# DAC_SUPPLY.net
KiCad netlist of a schematic drawn in Altium Designer
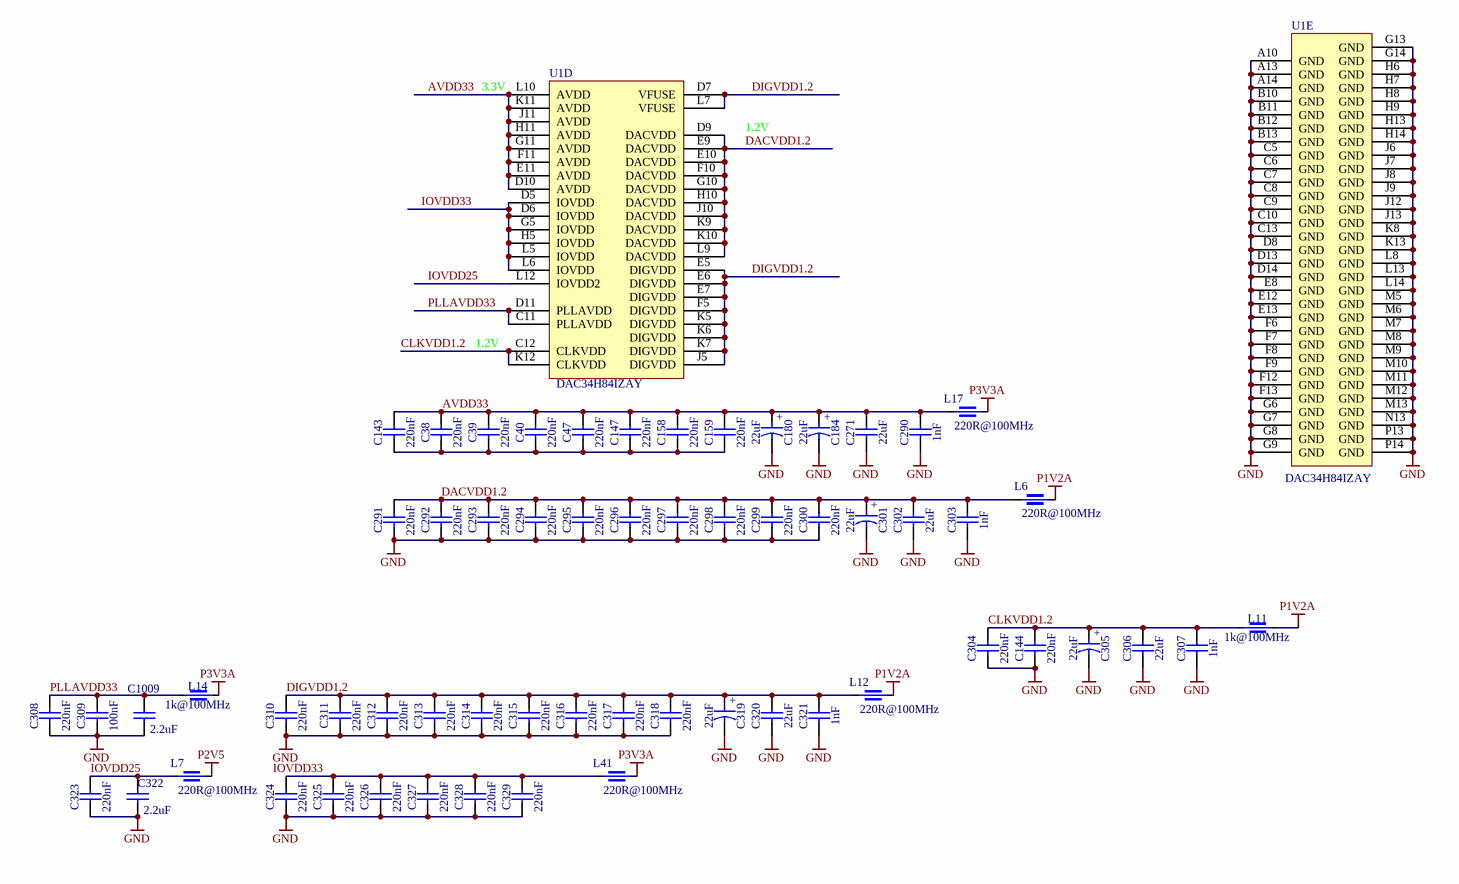
[diagram p0: DAC_SUPPLY.SchDoc]

(export (version "E")
  (design (tool "Eeschema 10.0.6"))
  (components
    (comp (ref "C38")
      (value "220nF")
      (footprint "CAPC0603X33N")
      (description "Non-polarised capacitor")
      (fields
        (field (name "PART NUMBER") "CC0201_220NF_6.3V_20%_X5R")
        (field (name "VOLTAGE") "6.3V")
        (field (name "AUTHOR") "CERN DEM JLC")
      )
      (libsource (lib "Capacitors") (part "Capacitor - non polarized"))
    )
    (comp (ref "C39")
      (value "220nF")
      (footprint "CAPC0603X33N")
      (description "Non-polarised capacitor")
      (fields
        (field (name "PART NUMBER") "CC0201_220NF_6.3V_20%_X5R")
        (field (name "VOLTAGE") "6.3V")
        (field (name "AUTHOR") "CERN DEM JLC")
      )
      (libsource (lib "Capacitors") (part "Capacitor - non polarized"))
    )
    (comp (ref "C40")
      (value "220nF")
      (footprint "CAPC0603X33N")
      (description "Non-polarised capacitor")
      (fields
        (field (name "PART NUMBER") "CC0201_220NF_6.3V_20%_X5R")
        (field (name "VOLTAGE") "6.3V")
        (field (name "AUTHOR") "CERN DEM JLC")
      )
      (libsource (lib "Capacitors") (part "Capacitor - non polarized"))
    )
    (comp (ref "C47")
      (value "220nF")
      (footprint "CAPC0603X33N")
      (description "Non-polarised capacitor")
      (fields
        (field (name "PART NUMBER") "CC0201_220NF_6.3V_20%_X5R")
        (field (name "VOLTAGE") "6.3V")
        (field (name "AUTHOR") "CERN DEM JLC")
      )
      (libsource (lib "Capacitors") (part "Capacitor - non polarized"))
    )
    (comp (ref "C143")
      (value "220nF")
      (footprint "CAPC0603X33N")
      (description "Non-polarised capacitor")
      (fields
        (field (name "PART NUMBER") "CC0201_220NF_6.3V_20%_X5R")
        (field (name "VOLTAGE") "6.3V")
        (field (name "AUTHOR") "CERN DEM JLC")
      )
      (libsource (lib "Capacitors") (part "Capacitor - non polarized"))
    )
    (comp (ref "C144")
      (value "220nF")
      (footprint "CAPC0603X33N")
      (description "Non-polarised capacitor")
      (fields
        (field (name "PART NUMBER") "CC0201_220NF_6.3V_20%_X5R")
        (field (name "VOLTAGE") "6.3V")
        (field (name "AUTHOR") "CERN DEM JLC")
      )
      (libsource (lib "Capacitors") (part "Capacitor - non polarized"))
    )
    (comp (ref "C147")
      (value "220nF")
      (footprint "CAPC0603X33N")
      (description "Non-polarised capacitor")
      (fields
        (field (name "PART NUMBER") "CC0201_220NF_6.3V_20%_X5R")
        (field (name "VOLTAGE") "6.3V")
        (field (name "AUTHOR") "CERN DEM JLC")
      )
      (libsource (lib "Capacitors") (part "Capacitor - non polarized"))
    )
    (comp (ref "C158")
      (value "220nF")
      (footprint "CAPC0603X33N")
      (description "Non-polarised capacitor")
      (fields
        (field (name "PART NUMBER") "CC0201_220NF_6.3V_20%_X5R")
        (field (name "VOLTAGE") "6.3V")
        (field (name "AUTHOR") "CERN DEM JLC")
      )
      (libsource (lib "Capacitors") (part "Capacitor - non polarized"))
    )
    (comp (ref "C159")
      (value "220nF")
      (footprint "CAPC0603X33N")
      (description "Non-polarised capacitor")
      (fields
        (field (name "PART NUMBER") "CC0201_220NF_6.3V_20%_X5R")
        (field (name "VOLTAGE") "6.3V")
        (field (name "AUTHOR") "CERN DEM JLC")
      )
      (libsource (lib "Capacitors") (part "Capacitor - non polarized"))
    )
    (comp (ref "C180")
      (value "22uF")
      (footprint "CAPMP3528X210N")
      (description "Polarised capacitor")
      (fields
        (field (name "PART NUMBER") "CTE3528-21_22UF_10V_10%_LESR0700")
        (field (name "VOLTAGE") "10V")
        (field (name "AUTHOR") "CERN DEM JLC")
      )
      (libsource (lib "Capacitors") (part "Capacitor - polarized"))
    )
    (comp (ref "C184")
      (value "22uF")
      (footprint "CAPMP3528X210N")
      (description "Polarised capacitor")
      (fields
        (field (name "PART NUMBER") "CTE3528-21_22UF_10V_10%_LESR0700")
        (field (name "VOLTAGE") "10V")
        (field (name "AUTHOR") "CERN DEM JLC")
      )
      (libsource (lib "Capacitors") (part "Capacitor - polarized"))
    )
    (comp (ref "C271")
      (value "22uF")
      (footprint "CAPC1709X100N")
      (description "Non-polarised capacitor")
      (fields
        (field (name "PART NUMBER") "CC0603_22UF_6.3V_20%_X5R")
        (field (name "VOLTAGE") "6.3V")
        (field (name "AUTHOR") "CERN DEM JLC")
      )
      (libsource (lib "Capacitors") (part "Capacitor - non polarized"))
    )
    (comp (ref "C290")
      (value "1nF")
      (footprint "CAPC1005X55N")
      (description "Non-polarised capacitor")
      (fields
        (field (name "PART NUMBER") "CC0402_1NF_50V_10%_X7R")
        (field (name "VOLTAGE") "50V")
        (field (name "AUTHOR") "CERN DEM JLC")
      )
      (libsource (lib "Capacitors") (part "Capacitor - non polarized"))
    )
    (comp (ref "C291")
      (value "220nF")
      (footprint "CAPC0603X33N")
      (description "Non-polarised capacitor")
      (fields
        (field (name "PART NUMBER") "CC0201_220NF_6.3V_20%_X5R")
        (field (name "VOLTAGE") "6.3V")
        (field (name "AUTHOR") "CERN DEM JLC")
      )
      (libsource (lib "Capacitors") (part "Capacitor - non polarized"))
    )
    (comp (ref "C292")
      (value "220nF")
      (footprint "CAPC0603X33N")
      (description "Non-polarised capacitor")
      (fields
        (field (name "PART NUMBER") "CC0201_220NF_6.3V_20%_X5R")
        (field (name "VOLTAGE") "6.3V")
        (field (name "AUTHOR") "CERN DEM JLC")
      )
      (libsource (lib "Capacitors") (part "Capacitor - non polarized"))
    )
    (comp (ref "C293")
      (value "220nF")
      (footprint "CAPC0603X33N")
      (description "Non-polarised capacitor")
      (fields
        (field (name "PART NUMBER") "CC0201_220NF_6.3V_20%_X5R")
        (field (name "VOLTAGE") "6.3V")
        (field (name "AUTHOR") "CERN DEM JLC")
      )
      (libsource (lib "Capacitors") (part "Capacitor - non polarized"))
    )
    (comp (ref "C294")
      (value "220nF")
      (footprint "CAPC0603X33N")
      (description "Non-polarised capacitor")
      (fields
        (field (name "PART NUMBER") "CC0201_220NF_6.3V_20%_X5R")
        (field (name "VOLTAGE") "6.3V")
        (field (name "AUTHOR") "CERN DEM JLC")
      )
      (libsource (lib "Capacitors") (part "Capacitor - non polarized"))
    )
    (comp (ref "C295")
      (value "220nF")
      (footprint "CAPC0603X33N")
      (description "Non-polarised capacitor")
      (fields
        (field (name "PART NUMBER") "CC0201_220NF_6.3V_20%_X5R")
        (field (name "VOLTAGE") "6.3V")
        (field (name "AUTHOR") "CERN DEM JLC")
      )
      (libsource (lib "Capacitors") (part "Capacitor - non polarized"))
    )
    (comp (ref "C296")
      (value "220nF")
      (footprint "CAPC0603X33N")
      (description "Non-polarised capacitor")
      (fields
        (field (name "PART NUMBER") "CC0201_220NF_6.3V_20%_X5R")
        (field (name "VOLTAGE") "6.3V")
        (field (name "AUTHOR") "CERN DEM JLC")
      )
      (libsource (lib "Capacitors") (part "Capacitor - non polarized"))
    )
    (comp (ref "C297")
      (value "220nF")
      (footprint "CAPC0603X33N")
      (description "Non-polarised capacitor")
      (fields
        (field (name "PART NUMBER") "CC0201_220NF_6.3V_20%_X5R")
        (field (name "VOLTAGE") "6.3V")
        (field (name "AUTHOR") "CERN DEM JLC")
      )
      (libsource (lib "Capacitors") (part "Capacitor - non polarized"))
    )
    (comp (ref "C298")
      (value "220nF")
      (footprint "CAPC0603X33N")
      (description "Non-polarised capacitor")
      (fields
        (field (name "PART NUMBER") "CC0201_220NF_6.3V_20%_X5R")
        (field (name "VOLTAGE") "6.3V")
        (field (name "AUTHOR") "CERN DEM JLC")
      )
      (libsource (lib "Capacitors") (part "Capacitor - non polarized"))
    )
    (comp (ref "C299")
      (value "220nF")
      (footprint "CAPC0603X33N")
      (description "Non-polarised capacitor")
      (fields
        (field (name "PART NUMBER") "CC0201_220NF_6.3V_20%_X5R")
        (field (name "VOLTAGE") "6.3V")
        (field (name "AUTHOR") "CERN DEM JLC")
      )
      (libsource (lib "Capacitors") (part "Capacitor - non polarized"))
    )
    (comp (ref "C300")
      (value "220nF")
      (footprint "CAPC0603X33N")
      (description "Non-polarised capacitor")
      (fields
        (field (name "PART NUMBER") "CC0201_220NF_6.3V_20%_X5R")
        (field (name "VOLTAGE") "6.3V")
        (field (name "AUTHOR") "CERN DEM JLC")
      )
      (libsource (lib "Capacitors") (part "Capacitor - non polarized"))
    )
    (comp (ref "C301")
      (value "22uF")
      (footprint "CAPMP3528X210N")
      (description "Polarised capacitor")
      (fields
        (field (name "PART NUMBER") "CTE3528-21_22UF_10V_10%_LESR0700")
        (field (name "VOLTAGE") "10V")
        (field (name "AUTHOR") "CERN DEM JLC")
      )
      (libsource (lib "Capacitors") (part "Capacitor - polarized"))
    )
    (comp (ref "C302")
      (value "22uF")
      (footprint "CAPC1709X100N")
      (description "Non-polarised capacitor")
      (fields
        (field (name "PART NUMBER") "CC0603_22UF_6.3V_20%_X5R")
        (field (name "VOLTAGE") "6.3V")
        (field (name "AUTHOR") "CERN DEM JLC")
      )
      (libsource (lib "Capacitors") (part "Capacitor - non polarized"))
    )
    (comp (ref "C303")
      (value "1nF")
      (footprint "CAPC1005X55N")
      (description "Non-polarised capacitor")
      (fields
        (field (name "PART NUMBER") "CC0402_1NF_50V_10%_X7R")
        (field (name "VOLTAGE") "50V")
        (field (name "AUTHOR") "CERN DEM JLC")
      )
      (libsource (lib "Capacitors") (part "Capacitor - non polarized"))
    )
    (comp (ref "C304")
      (value "220nF")
      (footprint "CAPC0603X33N")
      (description "Non-polarised capacitor")
      (fields
        (field (name "PART NUMBER") "CC0201_220NF_6.3V_20%_X5R")
        (field (name "VOLTAGE") "6.3V")
        (field (name "AUTHOR") "CERN DEM JLC")
      )
      (libsource (lib "Capacitors") (part "Capacitor - non polarized"))
    )
    (comp (ref "C305")
      (value "22uF")
      (footprint "CAPMP3528X210N")
      (description "Polarised capacitor")
      (fields
        (field (name "PART NUMBER") "CTE3528-21_22UF_10V_10%_LESR0700")
        (field (name "VOLTAGE") "10V")
        (field (name "AUTHOR") "CERN DEM JLC")
      )
      (libsource (lib "Capacitors") (part "Capacitor - polarized"))
    )
    (comp (ref "C306")
      (value "22uF")
      (footprint "CAPC1709X100N")
      (description "Non-polarised capacitor")
      (fields
        (field (name "PART NUMBER") "CC0603_22UF_6.3V_20%_X5R")
        (field (name "VOLTAGE") "6.3V")
        (field (name "AUTHOR") "CERN DEM JLC")
      )
      (libsource (lib "Capacitors") (part "Capacitor - non polarized"))
    )
    (comp (ref "C307")
      (value "1nF")
      (footprint "CAPC1005X55N")
      (description "Non-polarised capacitor")
      (fields
        (field (name "PART NUMBER") "CC0402_1NF_50V_10%_X7R")
        (field (name "VOLTAGE") "50V")
        (field (name "AUTHOR") "CERN DEM JLC")
      )
      (libsource (lib "Capacitors") (part "Capacitor - non polarized"))
    )
    (comp (ref "C308")
      (value "220nF")
      (footprint "CAPC0603X33N")
      (description "Non-polarised capacitor")
      (fields
        (field (name "PART NUMBER") "CC0201_220NF_6.3V_20%_X5R")
        (field (name "VOLTAGE") "6.3V")
        (field (name "AUTHOR") "CERN DEM JLC")
      )
      (libsource (lib "Capacitors") (part "Capacitor - non polarized"))
    )
    (comp (ref "C309")
      (value "100nF")
      (footprint "CAPC1608X90N")
      (description "Non-polarised capacitor")
      (fields
        (field (name "PART NUMBER") "CC0603_100NF_100V_10%_X7R")
        (field (name "VOLTAGE") "100V")
        (field (name "AUTHOR") "CERN DEM JLC")
      )
      (libsource (lib "Capacitors") (part "Capacitor - non polarized"))
    )
    (comp (ref "C310")
      (value "220nF")
      (footprint "CAPC0603X33N")
      (description "Non-polarised capacitor")
      (fields
        (field (name "PART NUMBER") "CC0201_220NF_6.3V_20%_X5R")
        (field (name "VOLTAGE") "6.3V")
        (field (name "AUTHOR") "CERN DEM JLC")
      )
      (libsource (lib "Capacitors") (part "Capacitor - non polarized"))
    )
    (comp (ref "C311")
      (value "220nF")
      (footprint "CAPC0603X33N")
      (description "Non-polarised capacitor")
      (fields
        (field (name "PART NUMBER") "CC0201_220NF_6.3V_20%_X5R")
        (field (name "VOLTAGE") "6.3V")
        (field (name "AUTHOR") "CERN DEM JLC")
      )
      (libsource (lib "Capacitors") (part "Capacitor - non polarized"))
    )
    (comp (ref "C312")
      (value "220nF")
      (footprint "CAPC0603X33N")
      (description "Non-polarised capacitor")
      (fields
        (field (name "PART NUMBER") "CC0201_220NF_6.3V_20%_X5R")
        (field (name "VOLTAGE") "6.3V")
        (field (name "AUTHOR") "CERN DEM JLC")
      )
      (libsource (lib "Capacitors") (part "Capacitor - non polarized"))
    )
    (comp (ref "C313")
      (value "220nF")
      (footprint "CAPC0603X33N")
      (description "Non-polarised capacitor")
      (fields
        (field (name "PART NUMBER") "CC0201_220NF_6.3V_20%_X5R")
        (field (name "VOLTAGE") "6.3V")
        (field (name "AUTHOR") "CERN DEM JLC")
      )
      (libsource (lib "Capacitors") (part "Capacitor - non polarized"))
    )
    (comp (ref "C314")
      (value "220nF")
      (footprint "CAPC0603X33N")
      (description "Non-polarised capacitor")
      (fields
        (field (name "PART NUMBER") "CC0201_220NF_6.3V_20%_X5R")
        (field (name "VOLTAGE") "6.3V")
        (field (name "AUTHOR") "CERN DEM JLC")
      )
      (libsource (lib "Capacitors") (part "Capacitor - non polarized"))
    )
    (comp (ref "C315")
      (value "220nF")
      (footprint "CAPC0603X33N")
      (description "Non-polarised capacitor")
      (fields
        (field (name "PART NUMBER") "CC0201_220NF_6.3V_20%_X5R")
        (field (name "VOLTAGE") "6.3V")
        (field (name "AUTHOR") "CERN DEM JLC")
      )
      (libsource (lib "Capacitors") (part "Capacitor - non polarized"))
    )
    (comp (ref "C316")
      (value "220nF")
      (footprint "CAPC0603X33N")
      (description "Non-polarised capacitor")
      (fields
        (field (name "PART NUMBER") "CC0201_220NF_6.3V_20%_X5R")
        (field (name "VOLTAGE") "6.3V")
        (field (name "AUTHOR") "CERN DEM JLC")
      )
      (libsource (lib "Capacitors") (part "Capacitor - non polarized"))
    )
    (comp (ref "C317")
      (value "220nF")
      (footprint "CAPC0603X33N")
      (description "Non-polarised capacitor")
      (fields
        (field (name "PART NUMBER") "CC0201_220NF_6.3V_20%_X5R")
        (field (name "VOLTAGE") "6.3V")
        (field (name "AUTHOR") "CERN DEM JLC")
      )
      (libsource (lib "Capacitors") (part "Capacitor - non polarized"))
    )
    (comp (ref "C318")
      (value "220nF")
      (footprint "CAPC0603X33N")
      (description "Non-polarised capacitor")
      (fields
        (field (name "PART NUMBER") "CC0201_220NF_6.3V_20%_X5R")
        (field (name "VOLTAGE") "6.3V")
        (field (name "AUTHOR") "CERN DEM JLC")
      )
      (libsource (lib "Capacitors") (part "Capacitor - non polarized"))
    )
    (comp (ref "C319")
      (value "22uF")
      (footprint "CAPMP3528X210N")
      (description "Polarised capacitor")
      (fields
        (field (name "PART NUMBER") "CTE3528-21_22UF_10V_10%_LESR0700")
        (field (name "VOLTAGE") "10V")
        (field (name "AUTHOR") "CERN DEM JLC")
      )
      (libsource (lib "Capacitors") (part "Capacitor - polarized"))
    )
    (comp (ref "C320")
      (value "22uF")
      (footprint "CAPC1709X100N")
      (description "Non-polarised capacitor")
      (fields
        (field (name "PART NUMBER") "CC0603_22UF_6.3V_20%_X5R")
        (field (name "VOLTAGE") "6.3V")
        (field (name "AUTHOR") "CERN DEM JLC")
      )
      (libsource (lib "Capacitors") (part "Capacitor - non polarized"))
    )
    (comp (ref "C321")
      (value "1nF")
      (footprint "CAPC1005X55N")
      (description "Non-polarised capacitor")
      (fields
        (field (name "PART NUMBER") "CC0402_1NF_50V_10%_X7R")
        (field (name "VOLTAGE") "50V")
        (field (name "AUTHOR") "CERN DEM JLC")
      )
      (libsource (lib "Capacitors") (part "Capacitor - non polarized"))
    )
    (comp (ref "C322")
      (value "2.2uF")
      (footprint "CAPC1005X55N")
      (description "Non-polarised capacitor")
      (fields
        (field (name "PART NUMBER") "CC0402_2.2UF_6.3V_10%_X5R")
        (field (name "VOLTAGE") "6.3V")
        (field (name "AUTHOR") "CERN DEM JMW")
      )
      (libsource (lib "Capacitors") (part "Capacitor - non polarized"))
    )
    (comp (ref "C323")
      (value "220nF")
      (footprint "CAPC0603X33N")
      (description "Non-polarised capacitor")
      (fields
        (field (name "PART NUMBER") "CC0201_220NF_6.3V_20%_X5R")
        (field (name "VOLTAGE") "6.3V")
        (field (name "AUTHOR") "CERN DEM JLC")
      )
      (libsource (lib "Capacitors") (part "Capacitor - non polarized"))
    )
    (comp (ref "C324")
      (value "220nF")
      (footprint "CAPC0603X33N")
      (description "Non-polarised capacitor")
      (fields
        (field (name "PART NUMBER") "CC0201_220NF_6.3V_20%_X5R")
        (field (name "VOLTAGE") "6.3V")
        (field (name "AUTHOR") "CERN DEM JLC")
      )
      (libsource (lib "Capacitors") (part "Capacitor - non polarized"))
    )
    (comp (ref "C325")
      (value "220nF")
      (footprint "CAPC0603X33N")
      (description "Non-polarised capacitor")
      (fields
        (field (name "PART NUMBER") "CC0201_220NF_6.3V_20%_X5R")
        (field (name "VOLTAGE") "6.3V")
        (field (name "AUTHOR") "CERN DEM JLC")
      )
      (libsource (lib "Capacitors") (part "Capacitor - non polarized"))
    )
    (comp (ref "C326")
      (value "220nF")
      (footprint "CAPC0603X33N")
      (description "Non-polarised capacitor")
      (fields
        (field (name "PART NUMBER") "CC0201_220NF_6.3V_20%_X5R")
        (field (name "VOLTAGE") "6.3V")
        (field (name "AUTHOR") "CERN DEM JLC")
      )
      (libsource (lib "Capacitors") (part "Capacitor - non polarized"))
    )
    (comp (ref "C327")
      (value "220nF")
      (footprint "CAPC0603X33N")
      (description "Non-polarised capacitor")
      (fields
        (field (name "PART NUMBER") "CC0201_220NF_6.3V_20%_X5R")
        (field (name "VOLTAGE") "6.3V")
        (field (name "AUTHOR") "CERN DEM JLC")
      )
      (libsource (lib "Capacitors") (part "Capacitor - non polarized"))
    )
    (comp (ref "C328")
      (value "220nF")
      (footprint "CAPC0603X33N")
      (description "Non-polarised capacitor")
      (fields
        (field (name "PART NUMBER") "CC0201_220NF_6.3V_20%_X5R")
        (field (name "VOLTAGE") "6.3V")
        (field (name "AUTHOR") "CERN DEM JLC")
      )
      (libsource (lib "Capacitors") (part "Capacitor - non polarized"))
    )
    (comp (ref "C329")
      (value "220nF")
      (footprint "CAPC0603X33N")
      (description "Non-polarised capacitor")
      (fields
        (field (name "PART NUMBER") "CC0201_220NF_6.3V_20%_X5R")
        (field (name "VOLTAGE") "6.3V")
        (field (name "AUTHOR") "CERN DEM JLC")
      )
      (libsource (lib "Capacitors") (part "Capacitor - non polarized"))
    )
    (comp (ref "C1009")
      (value "2.2uF")
      (footprint "CAPC1005X55N")
      (description "Non-polarised capacitor")
      (fields
        (field (name "PART NUMBER") "CC0402_2.2UF_6.3V_10%_X5R")
        (field (name "VOLTAGE") "6.3V")
        (field (name "AUTHOR") "CERN DEM JMW")
      )
      (libsource (lib "Capacitors") (part "Capacitor - non polarized"))
    )
    (comp (ref "L6")
      (value "220R@100MHz")
      (footprint "INDC1608X95N")
      (fields
        (field (name "PART NUMBER") "IND0603_MURATA_BLM18SG221TN1")
        (field (name "POWER") "2.5A")
        (field (name "TOLERANCE") "±25%")
        (field (name "AUTHOR") "CERN DEM MR")
      )
      (libsource (lib "Inductors & Transformers") (part "Ferrite Bead"))
    )
    (comp (ref "L7")
      (value "220R@100MHz")
      (footprint "INDC1608X95N")
      (fields
        (field (name "PART NUMBER") "IND0603_MURATA_BLM18SG221TN1")
        (field (name "POWER") "2.5A")
        (field (name "TOLERANCE") "±25%")
        (field (name "AUTHOR") "CERN DEM MR")
      )
      (libsource (lib "Inductors & Transformers") (part "Ferrite Bead"))
    )
    (comp (ref "L11")
      (value "1k@100MHz")
      (footprint "INDC1005X55N")
      (fields
        (field (name "PART NUMBER") "IND0402_MURATA_BLM15HD102SN1")
        (field (name "POWER") "250mA")
        (field (name "TOLERANCE") "±25%")
        (field (name "AUTHOR") "CERN DEM JLC")
      )
      (libsource (lib "Inductors & Transformers") (part "Ferrite Bead"))
    )
    (comp (ref "L12")
      (value "220R@100MHz")
      (footprint "INDC1608X95N")
      (fields
        (field (name "PART NUMBER") "IND0603_MURATA_BLM18SG221TN1")
        (field (name "POWER") "2.5A")
        (field (name "TOLERANCE") "±25%")
        (field (name "AUTHOR") "CERN DEM MR")
      )
      (libsource (lib "Inductors & Transformers") (part "Ferrite Bead"))
    )
    (comp (ref "L14")
      (value "1k@100MHz")
      (footprint "INDC1005X55N")
      (fields
        (field (name "PART NUMBER") "IND0402_MURATA_BLM15HD102SN1")
        (field (name "POWER") "250mA")
        (field (name "TOLERANCE") "±25%")
        (field (name "AUTHOR") "CERN DEM JLC")
      )
      (libsource (lib "Inductors & Transformers") (part "Ferrite Bead"))
    )
    (comp (ref "L17")
      (value "220R@100MHz")
      (footprint "INDC1608X95N")
      (fields
        (field (name "PART NUMBER") "IND0603_MURATA_BLM18SG221TN1")
        (field (name "POWER") "2.5A")
        (field (name "TOLERANCE") "±25%")
        (field (name "AUTHOR") "CERN DEM MR")
      )
      (libsource (lib "Inductors & Transformers") (part "Ferrite Bead"))
    )
    (comp (ref "L41")
      (value "220R@100MHz")
      (footprint "INDC1608X95N")
      (fields
        (field (name "PART NUMBER") "IND0603_MURATA_BLM18SG221TN1")
        (field (name "POWER") "2.5A")
        (field (name "TOLERANCE") "±25%")
        (field (name "AUTHOR") "CERN DEM MR")
      )
      (libsource (lib "Inductors & Transformers") (part "Ferrite Bead"))
    )
    (comp (ref "U1")
      (value "DAC34H84IZAY")
      (footprint "TI-ZAY196")
      (description "Quad-Channel, 16-Bit, 1.5 GSPS DAC, -40 to 85 degC, 196-pin BGA (ZAY196), Green (RoHS & no Sb/Br)")
      (fields (field (name "MANUFACTURER") "Texas Instruments"))
      (libsource (lib "Altium Content Vault") (part "TI-DAC34H_SH84-ZAY196"))
    )
  )
  (nets
    (net (code "1") (name "/AVDD33") (class "Default")
      (node (ref "C143") (pin "2") (pinfunction "2_2") (pintype "passive"))
      (node (ref "C147") (pin "2") (pinfunction "2_2") (pintype "passive"))
      (node (ref "C158") (pin "2") (pinfunction "2_2") (pintype "passive"))
      (node (ref "C159") (pin "2") (pinfunction "2_2") (pintype "passive"))
      (node (ref "C180") (pin "1") (pinfunction "1_1") (pintype "passive"))
      (node (ref "C184") (pin "1") (pinfunction "1_1") (pintype "passive"))
      (node (ref "C271") (pin "2") (pinfunction "2_2") (pintype "passive"))
      (node (ref "C290") (pin "2") (pinfunction "2_2") (pintype "passive"))
      (node (ref "C38") (pin "2") (pinfunction "2_2") (pintype "passive"))
      (node (ref "C39") (pin "2") (pinfunction "2_2") (pintype "passive"))
      (node (ref "C40") (pin "2") (pinfunction "2_2") (pintype "passive"))
      (node (ref "C47") (pin "2") (pinfunction "2_2") (pintype "passive"))
      (node (ref "L17") (pin "1") (pinfunction "1_1") (pintype "passive"))
      (node (ref "U1") (pin "D10") (pinfunction "AVDD_D10") (pintype "power_in"))
      (node (ref "U1") (pin "E11") (pinfunction "AVDD_E11") (pintype "power_in"))
      (node (ref "U1") (pin "F11") (pinfunction "AVDD_F11") (pintype "power_in"))
      (node (ref "U1") (pin "G11") (pinfunction "AVDD_G11") (pintype "power_in"))
      (node (ref "U1") (pin "H11") (pinfunction "AVDD_H11") (pintype "power_in"))
      (node (ref "U1") (pin "J11") (pinfunction "AVDD_J11") (pintype "power_in"))
      (node (ref "U1") (pin "K11") (pinfunction "AVDD_K11") (pintype "power_in"))
      (node (ref "U1") (pin "L10") (pinfunction "AVDD_L10") (pintype "power_in"))
    )
    (net (code "2") (name "/CLKVDD1.2") (class "Default")
      (node (ref "C144") (pin "2") (pinfunction "2_2") (pintype "passive"))
      (node (ref "C304") (pin "2") (pinfunction "2_2") (pintype "passive"))
      (node (ref "C305") (pin "1") (pinfunction "1_1") (pintype "passive"))
      (node (ref "C306") (pin "2") (pinfunction "2_2") (pintype "passive"))
      (node (ref "C307") (pin "2") (pinfunction "2_2") (pintype "passive"))
      (node (ref "L11") (pin "1") (pinfunction "1_1") (pintype "passive"))
      (node (ref "U1") (pin "C12") (pinfunction "CLKVDD_C12") (pintype "power_in"))
      (node (ref "U1") (pin "K12") (pinfunction "CLKVDD_K12") (pintype "power_in"))
    )
    (net (code "3") (name "/DACVDD1.2") (class "Default")
      (node (ref "C291") (pin "2") (pinfunction "2_2") (pintype "passive"))
      (node (ref "C292") (pin "2") (pinfunction "2_2") (pintype "passive"))
      (node (ref "C293") (pin "2") (pinfunction "2_2") (pintype "passive"))
      (node (ref "C294") (pin "2") (pinfunction "2_2") (pintype "passive"))
      (node (ref "C295") (pin "2") (pinfunction "2_2") (pintype "passive"))
      (node (ref "C296") (pin "2") (pinfunction "2_2") (pintype "passive"))
      (node (ref "C297") (pin "2") (pinfunction "2_2") (pintype "passive"))
      (node (ref "C298") (pin "2") (pinfunction "2_2") (pintype "passive"))
      (node (ref "C299") (pin "2") (pinfunction "2_2") (pintype "passive"))
      (node (ref "C300") (pin "2") (pinfunction "2_2") (pintype "passive"))
      (node (ref "C301") (pin "1") (pinfunction "1_1") (pintype "passive"))
      (node (ref "C302") (pin "2") (pinfunction "2_2") (pintype "passive"))
      (node (ref "C303") (pin "2") (pinfunction "2_2") (pintype "passive"))
      (node (ref "L6") (pin "1") (pinfunction "1_1") (pintype "passive"))
      (node (ref "U1") (pin "D9") (pinfunction "DACVDD_D9") (pintype "power_in"))
      (node (ref "U1") (pin "E10") (pinfunction "DACVDD_E10") (pintype "power_in"))
      (node (ref "U1") (pin "E9") (pinfunction "DACVDD_E9") (pintype "power_in"))
      (node (ref "U1") (pin "F10") (pinfunction "DACVDD_F10") (pintype "power_in"))
      (node (ref "U1") (pin "G10") (pinfunction "DACVDD_G10") (pintype "power_in"))
      (node (ref "U1") (pin "H10") (pinfunction "DACVDD_H10") (pintype "power_in"))
      (node (ref "U1") (pin "J10") (pinfunction "DACVDD_J10") (pintype "power_in"))
      (node (ref "U1") (pin "K10") (pinfunction "DACVDD_K10") (pintype "power_in"))
      (node (ref "U1") (pin "K9") (pinfunction "DACVDD_K9") (pintype "power_in"))
      (node (ref "U1") (pin "L9") (pinfunction "DACVDD_L9") (pintype "power_in"))
    )
    (net (code "4") (name "/DIGVDD1.2") (class "Default")
      (node (ref "C310") (pin "2") (pinfunction "2_2") (pintype "passive"))
      (node (ref "C311") (pin "2") (pinfunction "2_2") (pintype "passive"))
      (node (ref "C312") (pin "2") (pinfunction "2_2") (pintype "passive"))
      (node (ref "C313") (pin "2") (pinfunction "2_2") (pintype "passive"))
      (node (ref "C314") (pin "2") (pinfunction "2_2") (pintype "passive"))
      (node (ref "C315") (pin "2") (pinfunction "2_2") (pintype "passive"))
      (node (ref "C316") (pin "2") (pinfunction "2_2") (pintype "passive"))
      (node (ref "C317") (pin "2") (pinfunction "2_2") (pintype "passive"))
      (node (ref "C318") (pin "2") (pinfunction "2_2") (pintype "passive"))
      (node (ref "C319") (pin "1") (pinfunction "1_1") (pintype "passive"))
      (node (ref "C320") (pin "2") (pinfunction "2_2") (pintype "passive"))
      (node (ref "C321") (pin "2") (pinfunction "2_2") (pintype "passive"))
      (node (ref "L12") (pin "1") (pinfunction "1_1") (pintype "passive"))
      (node (ref "U1") (pin "D7") (pinfunction "VFUSE_D7") (pintype "power_in"))
      (node (ref "U1") (pin "E5") (pinfunction "DIGVDD_E5") (pintype "power_in"))
      (node (ref "U1") (pin "E6") (pinfunction "DIGVDD_E6") (pintype "power_in"))
      (node (ref "U1") (pin "E7") (pinfunction "DIGVDD_E7") (pintype "power_in"))
      (node (ref "U1") (pin "F5") (pinfunction "DIGVDD_F5") (pintype "power_in"))
      (node (ref "U1") (pin "J5") (pinfunction "DIGVDD_J5") (pintype "power_in"))
      (node (ref "U1") (pin "K5") (pinfunction "DIGVDD_K5") (pintype "power_in"))
      (node (ref "U1") (pin "K6") (pinfunction "DIGVDD_K6") (pintype "power_in"))
      (node (ref "U1") (pin "K7") (pinfunction "DIGVDD_K7") (pintype "power_in"))
      (node (ref "U1") (pin "L7") (pinfunction "VFUSE_L7") (pintype "power_in"))
    )
    (net (code "5") (name "/IOVDD25") (class "Default")
      (node (ref "C322") (pin "2") (pinfunction "2_2") (pintype "passive"))
      (node (ref "C323") (pin "2") (pinfunction "2_2") (pintype "passive"))
      (node (ref "L7") (pin "1") (pinfunction "1_1") (pintype "passive"))
      (node (ref "U1") (pin "L12") (pinfunction "IOVDD2_L12") (pintype "power_in"))
    )
    (net (code "6") (name "/IOVDD33") (class "Default")
      (node (ref "U1") (pin "D5") (pinfunction "IOVDD_D5") (pintype "power_in"))
      (node (ref "U1") (pin "D6") (pinfunction "IOVDD_D6") (pintype "power_in"))
      (node (ref "U1") (pin "G5") (pinfunction "IOVDD_G5") (pintype "power_in"))
      (node (ref "U1") (pin "H5") (pinfunction "IOVDD_H5") (pintype "power_in"))
      (node (ref "U1") (pin "L5") (pinfunction "IOVDD_L5") (pintype "power_in"))
      (node (ref "U1") (pin "L6") (pinfunction "IOVDD_L6") (pintype "power_in"))
    )
    (net (code "7") (name "/PLLAVDD33") (class "Default")
      (node (ref "C1009") (pin "2") (pinfunction "2_2") (pintype "passive"))
      (node (ref "C308") (pin "2") (pinfunction "2_2") (pintype "passive"))
      (node (ref "C309") (pin "2") (pinfunction "2_2") (pintype "passive"))
      (node (ref "L14") (pin "1") (pinfunction "1_1") (pintype "passive"))
      (node (ref "U1") (pin "C11") (pinfunction "PLLAVDD_C11") (pintype "power_in"))
      (node (ref "U1") (pin "D11") (pinfunction "PLLAVDD_D11") (pintype "power_in"))
    )
    (net (code "8") (name "GND") (class "Default")
      (node (ref "C1009") (pin "1") (pinfunction "1_1") (pintype "passive"))
      (node (ref "C144") (pin "1") (pinfunction "1_1") (pintype "passive"))
      (node (ref "C180") (pin "2") (pinfunction "2_2") (pintype "passive"))
      (node (ref "C184") (pin "2") (pinfunction "2_2") (pintype "passive"))
      (node (ref "C271") (pin "1") (pinfunction "1_1") (pintype "passive"))
      (node (ref "C290") (pin "1") (pinfunction "1_1") (pintype "passive"))
      (node (ref "C291") (pin "1") (pinfunction "1_1") (pintype "passive"))
      (node (ref "C292") (pin "1") (pinfunction "1_1") (pintype "passive"))
      (node (ref "C293") (pin "1") (pinfunction "1_1") (pintype "passive"))
      (node (ref "C294") (pin "1") (pinfunction "1_1") (pintype "passive"))
      (node (ref "C295") (pin "1") (pinfunction "1_1") (pintype "passive"))
      (node (ref "C296") (pin "1") (pinfunction "1_1") (pintype "passive"))
      (node (ref "C297") (pin "1") (pinfunction "1_1") (pintype "passive"))
      (node (ref "C298") (pin "1") (pinfunction "1_1") (pintype "passive"))
      (node (ref "C299") (pin "1") (pinfunction "1_1") (pintype "passive"))
      (node (ref "C300") (pin "1") (pinfunction "1_1") (pintype "passive"))
      (node (ref "C301") (pin "2") (pinfunction "2_2") (pintype "passive"))
      (node (ref "C302") (pin "1") (pinfunction "1_1") (pintype "passive"))
      (node (ref "C303") (pin "1") (pinfunction "1_1") (pintype "passive"))
      (node (ref "C304") (pin "1") (pinfunction "1_1") (pintype "passive"))
      (node (ref "C305") (pin "2") (pinfunction "2_2") (pintype "passive"))
      (node (ref "C306") (pin "1") (pinfunction "1_1") (pintype "passive"))
      (node (ref "C307") (pin "1") (pinfunction "1_1") (pintype "passive"))
      (node (ref "C308") (pin "1") (pinfunction "1_1") (pintype "passive"))
      (node (ref "C309") (pin "1") (pinfunction "1_1") (pintype "passive"))
      (node (ref "C310") (pin "1") (pinfunction "1_1") (pintype "passive"))
      (node (ref "C311") (pin "1") (pinfunction "1_1") (pintype "passive"))
      (node (ref "C312") (pin "1") (pinfunction "1_1") (pintype "passive"))
      (node (ref "C313") (pin "1") (pinfunction "1_1") (pintype "passive"))
      (node (ref "C314") (pin "1") (pinfunction "1_1") (pintype "passive"))
      (node (ref "C315") (pin "1") (pinfunction "1_1") (pintype "passive"))
      (node (ref "C316") (pin "1") (pinfunction "1_1") (pintype "passive"))
      (node (ref "C317") (pin "1") (pinfunction "1_1") (pintype "passive"))
      (node (ref "C318") (pin "1") (pinfunction "1_1") (pintype "passive"))
      (node (ref "C319") (pin "2") (pinfunction "2_2") (pintype "passive"))
      (node (ref "C320") (pin "1") (pinfunction "1_1") (pintype "passive"))
      (node (ref "C321") (pin "1") (pinfunction "1_1") (pintype "passive"))
      (node (ref "C322") (pin "1") (pinfunction "1_1") (pintype "passive"))
      (node (ref "C323") (pin "1") (pinfunction "1_1") (pintype "passive"))
      (node (ref "C324") (pin "1") (pinfunction "1_1") (pintype "passive"))
      (node (ref "C325") (pin "1") (pinfunction "1_1") (pintype "passive"))
      (node (ref "C326") (pin "1") (pinfunction "1_1") (pintype "passive"))
      (node (ref "C327") (pin "1") (pinfunction "1_1") (pintype "passive"))
      (node (ref "C328") (pin "1") (pinfunction "1_1") (pintype "passive"))
      (node (ref "C329") (pin "1") (pinfunction "1_1") (pintype "passive"))
      (node (ref "U1") (pin "A10") (pinfunction "GND_A10") (pintype "power_in"))
      (node (ref "U1") (pin "A13") (pinfunction "GND_A13") (pintype "power_in"))
      (node (ref "U1") (pin "A14") (pinfunction "GND_A14") (pintype "power_in"))
      (node (ref "U1") (pin "B10") (pinfunction "GND_B10") (pintype "power_in"))
      (node (ref "U1") (pin "B11") (pinfunction "GND_B11") (pintype "power_in"))
      (node (ref "U1") (pin "B12") (pinfunction "GND_B12") (pintype "power_in"))
      (node (ref "U1") (pin "B13") (pinfunction "GND_B13") (pintype "power_in"))
      (node (ref "U1") (pin "C10") (pinfunction "GND_C10") (pintype "power_in"))
      (node (ref "U1") (pin "C13") (pinfunction "GND_C13") (pintype "power_in"))
      (node (ref "U1") (pin "C5") (pinfunction "GND_C5") (pintype "power_in"))
      (node (ref "U1") (pin "C6") (pinfunction "GND_C6") (pintype "power_in"))
      (node (ref "U1") (pin "C7") (pinfunction "GND_C7") (pintype "power_in"))
      (node (ref "U1") (pin "C8") (pinfunction "GND_C8") (pintype "power_in"))
      (node (ref "U1") (pin "C9") (pinfunction "GND_C9") (pintype "power_in"))
      (node (ref "U1") (pin "D13") (pinfunction "GND_D13") (pintype "power_in"))
      (node (ref "U1") (pin "D14") (pinfunction "GND_D14") (pintype "power_in"))
      (node (ref "U1") (pin "D8") (pinfunction "GND_D8") (pintype "power_in"))
      (node (ref "U1") (pin "E12") (pinfunction "GND_E12") (pintype "power_in"))
      (node (ref "U1") (pin "E13") (pinfunction "GND_E13") (pintype "power_in"))
      (node (ref "U1") (pin "E8") (pinfunction "GND_E8") (pintype "power_in"))
      (node (ref "U1") (pin "F12") (pinfunction "GND_F12") (pintype "power_in"))
      (node (ref "U1") (pin "F13") (pinfunction "GND_F13") (pintype "power_in"))
      (node (ref "U1") (pin "F6") (pinfunction "GND_F6") (pintype "power_in"))
      (node (ref "U1") (pin "F7") (pinfunction "GND_F7") (pintype "power_in"))
      (node (ref "U1") (pin "F8") (pinfunction "GND_F8") (pintype "power_in"))
      (node (ref "U1") (pin "F9") (pinfunction "GND_F9") (pintype "power_in"))
      (node (ref "U1") (pin "G13") (pinfunction "GND_G13") (pintype "power_in"))
      (node (ref "U1") (pin "G14") (pinfunction "GND_G14") (pintype "power_in"))
      (node (ref "U1") (pin "G6") (pinfunction "GND_G6") (pintype "power_in"))
      (node (ref "U1") (pin "G7") (pinfunction "GND_G7") (pintype "power_in"))
      (node (ref "U1") (pin "G8") (pinfunction "GND_G8") (pintype "power_in"))
      (node (ref "U1") (pin "G9") (pinfunction "GND_G9") (pintype "power_in"))
      (node (ref "U1") (pin "H13") (pinfunction "GND_H13") (pintype "power_in"))
      (node (ref "U1") (pin "H14") (pinfunction "GND_H14") (pintype "power_in"))
      (node (ref "U1") (pin "H6") (pinfunction "GND_H6") (pintype "power_in"))
      (node (ref "U1") (pin "H7") (pinfunction "GND_H7") (pintype "power_in"))
      (node (ref "U1") (pin "H8") (pinfunction "GND_H8") (pintype "power_in"))
      (node (ref "U1") (pin "H9") (pinfunction "GND_H9") (pintype "power_in"))
      (node (ref "U1") (pin "J12") (pinfunction "GND_J12") (pintype "power_in"))
      (node (ref "U1") (pin "J13") (pinfunction "GND_J13") (pintype "power_in"))
      (node (ref "U1") (pin "J6") (pinfunction "GND_J6") (pintype "power_in"))
      (node (ref "U1") (pin "J7") (pinfunction "GND_J7") (pintype "power_in"))
      (node (ref "U1") (pin "J8") (pinfunction "GND_J8") (pintype "power_in"))
      (node (ref "U1") (pin "J9") (pinfunction "GND_J9") (pintype "power_in"))
      (node (ref "U1") (pin "K13") (pinfunction "GND_K13") (pintype "power_in"))
      (node (ref "U1") (pin "K8") (pinfunction "GND_K8") (pintype "power_in"))
      (node (ref "U1") (pin "L13") (pinfunction "GND_L13") (pintype "power_in"))
      (node (ref "U1") (pin "L14") (pinfunction "GND_L14") (pintype "power_in"))
      (node (ref "U1") (pin "L8") (pinfunction "GND_L8") (pintype "power_in"))
      (node (ref "U1") (pin "M10") (pinfunction "GND_M10") (pintype "power_in"))
      (node (ref "U1") (pin "M11") (pinfunction "GND_M11") (pintype "power_in"))
      (node (ref "U1") (pin "M12") (pinfunction "GND_M12") (pintype "power_in"))
      (node (ref "U1") (pin "M13") (pinfunction "GND_M13") (pintype "power_in"))
      (node (ref "U1") (pin "M5") (pinfunction "GND_M5") (pintype "power_in"))
      (node (ref "U1") (pin "M6") (pinfunction "GND_M6") (pintype "power_in"))
      (node (ref "U1") (pin "M7") (pinfunction "GND_M7") (pintype "power_in"))
      (node (ref "U1") (pin "M8") (pinfunction "GND_M8") (pintype "power_in"))
      (node (ref "U1") (pin "M9") (pinfunction "GND_M9") (pintype "power_in"))
      (node (ref "U1") (pin "N13") (pinfunction "GND_N13") (pintype "power_in"))
      (node (ref "U1") (pin "P13") (pinfunction "GND_P13") (pintype "power_in"))
      (node (ref "U1") (pin "P14") (pinfunction "GND_P14") (pintype "power_in"))
    )
    (net (code "9") (name "Net-(C143-Pad1)") (class "Default")
      (node (ref "C143") (pin "1") (pinfunction "1_1") (pintype "passive"))
      (node (ref "C147") (pin "1") (pinfunction "1_1") (pintype "passive"))
      (node (ref "C158") (pin "1") (pinfunction "1_1") (pintype "passive"))
      (node (ref "C159") (pin "1") (pinfunction "1_1") (pintype "passive"))
      (node (ref "C38") (pin "1") (pinfunction "1_1") (pintype "passive"))
      (node (ref "C39") (pin "1") (pinfunction "1_1") (pintype "passive"))
      (node (ref "C40") (pin "1") (pinfunction "1_1") (pintype "passive"))
      (node (ref "C47") (pin "1") (pinfunction "1_1") (pintype "passive"))
    )
    (net (code "10") (name "Net-(C324-Pad2)") (class "Default")
      (node (ref "C324") (pin "2") (pinfunction "2_2") (pintype "passive"))
      (node (ref "C325") (pin "2") (pinfunction "2_2") (pintype "passive"))
      (node (ref "C326") (pin "2") (pinfunction "2_2") (pintype "passive"))
      (node (ref "C327") (pin "2") (pinfunction "2_2") (pintype "passive"))
      (node (ref "C328") (pin "2") (pinfunction "2_2") (pintype "passive"))
      (node (ref "C329") (pin "2") (pinfunction "2_2") (pintype "passive"))
      (node (ref "L41") (pin "1") (pinfunction "1_1") (pintype "passive"))
    )
    (net (code "11") (name "P1V2A") (class "Default")
      (node (ref "L11") (pin "2") (pinfunction "2_2") (pintype "passive"))
      (node (ref "L12") (pin "2") (pinfunction "2_2") (pintype "passive"))
      (node (ref "L6") (pin "2") (pinfunction "2_2") (pintype "passive"))
    )
    (net (code "12") (name "P2V5") (class "Default")
      (node (ref "L7") (pin "2") (pinfunction "2_2") (pintype "passive"))
    )
    (net (code "13") (name "P3V3A") (class "Default")
      (node (ref "L14") (pin "2") (pinfunction "2_2") (pintype "passive"))
      (node (ref "L17") (pin "2") (pinfunction "2_2") (pintype "passive"))
      (node (ref "L41") (pin "2") (pinfunction "2_2") (pintype "passive"))
    )
  )
)
